# onee_rev1.net
KiCad netlist of a schematic drawn in EAGLE
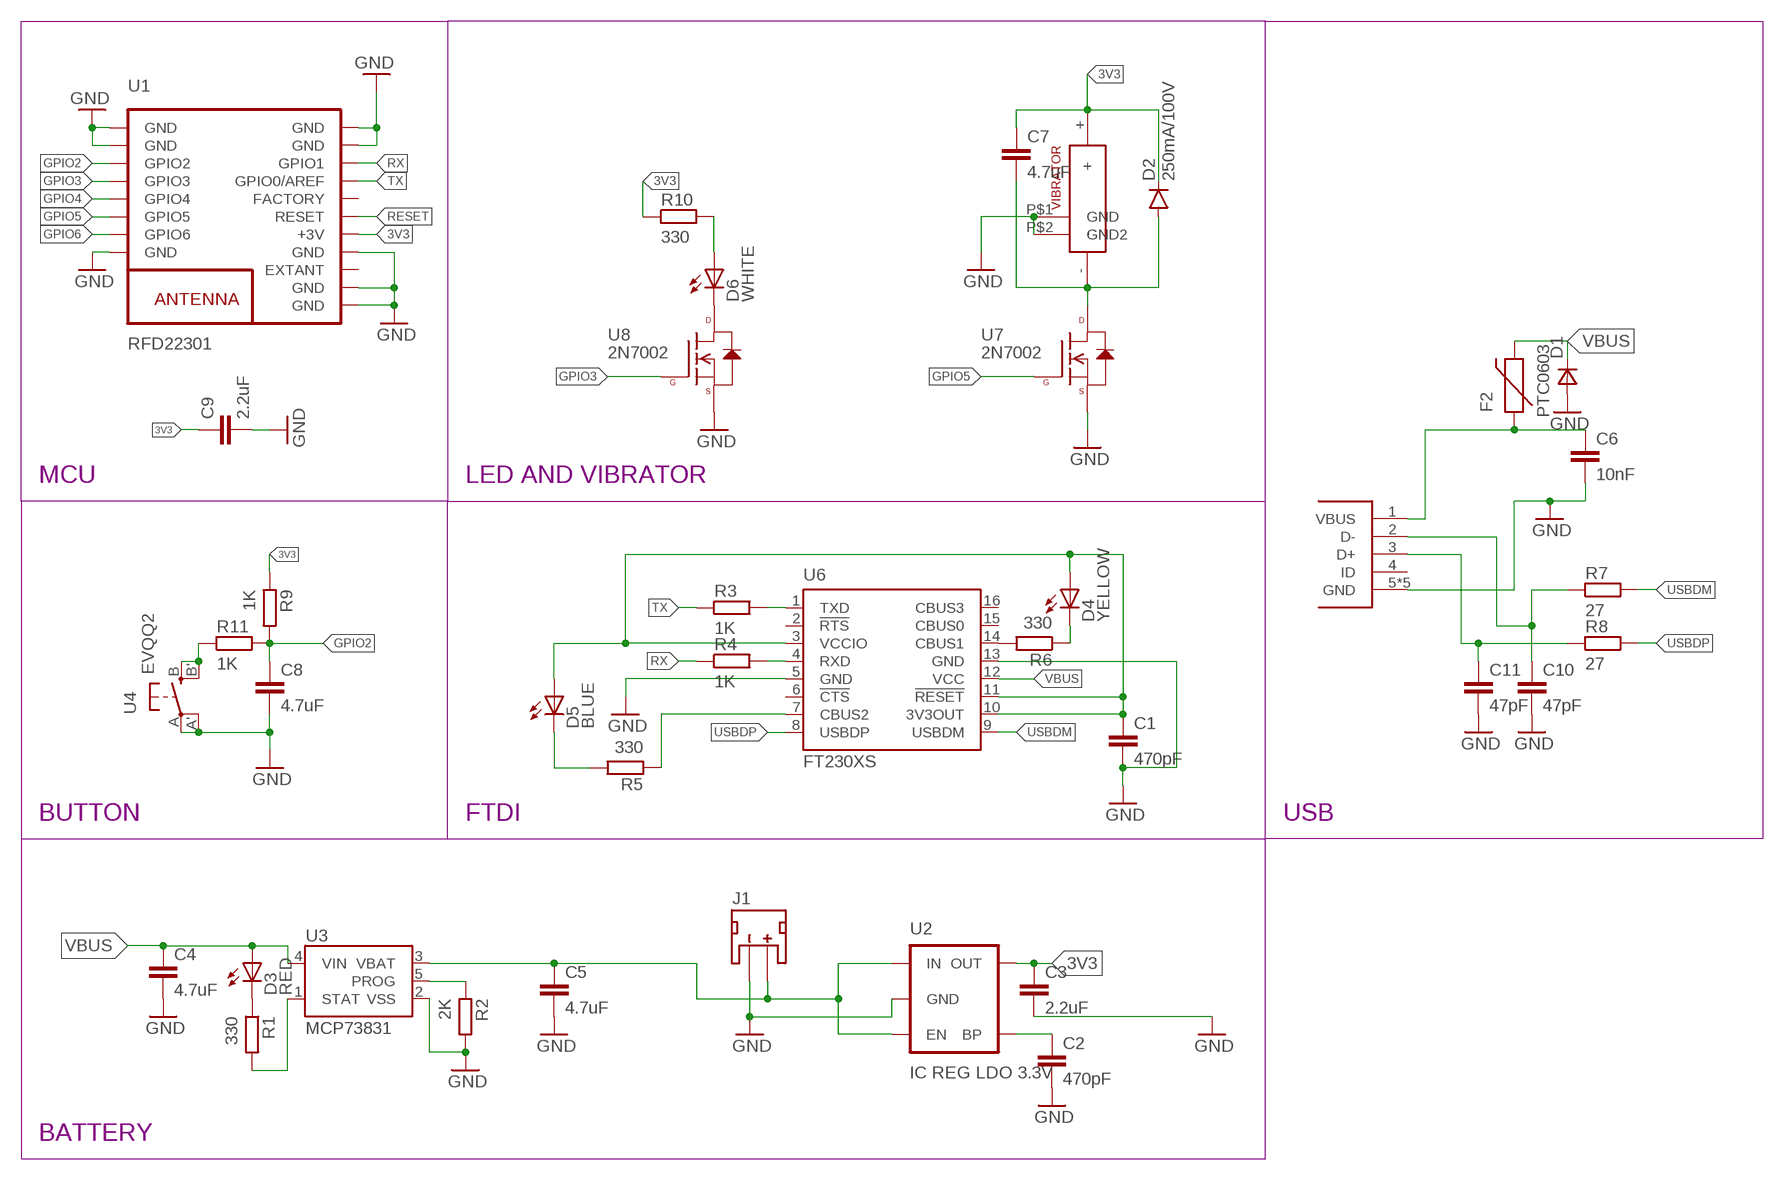
[diagram p0: schematic, sheet 1]

(export (version "E")
  (design (tool "Eeschema 10.0.6"))
  (components
    (comp (ref "C1")
      (value "470pF")
      (footprint "eagle-import:0603-CAP")
      (libsource (lib "eagle-import") (part "470PF-50V-5%(0603)SMD"))
    )
    (comp (ref "C2")
      (value "470pF")
      (footprint "eagle-import:0603-CAP")
      (libsource (lib "eagle-import") (part "470PF-50V-5%(0603)SMD"))
    )
    (comp (ref "C3")
      (value "2.2uF")
      (footprint "eagle-import:0603-CAP")
      (libsource (lib "eagle-import") (part "2.2UF-10V-20%(0603)"))
    )
    (comp (ref "C4")
      (value "4.7uF")
      (footprint "eagle-import:0603-CAP")
      (libsource (lib "eagle-import") (part "4.7UF-6.3V-10%(0603)0603"))
    )
    (comp (ref "C5")
      (value "4.7uF")
      (footprint "eagle-import:0603-CAP")
      (libsource (lib "eagle-import") (part "4.7UF-6.3V-10%(0603)0603"))
    )
    (comp (ref "C6")
      (value "10nF")
      (footprint "eagle-import:0603-CAP")
      (libsource (lib "eagle-import") (part "10NF/10000PF-50V-10%(0603)"))
    )
    (comp (ref "C7")
      (value "4.7uF")
      (footprint "eagle-import:0603-CAP")
      (libsource (lib "eagle-import") (part "4.7UF-6.3V-10%(0603)0603"))
    )
    (comp (ref "C8")
      (value "4.7uF")
      (footprint "eagle-import:0603-CAP")
      (libsource (lib "eagle-import") (part "4.7UF-6.3V-10%(0603)0603"))
    )
    (comp (ref "C9")
      (value "2.2uF")
      (footprint "eagle-import:0603-CAP")
      (libsource (lib "eagle-import") (part "2.2UF-10V-20%(0603)"))
    )
    (comp (ref "C10")
      (value "47pF")
      (footprint "eagle-import:0603-CAP")
      (libsource (lib "eagle-import") (part "47PF-50V-5%(0603)"))
    )
    (comp (ref "C11")
      (value "47pF")
      (footprint "eagle-import:0603-CAP")
      (libsource (lib "eagle-import") (part "47PF-50V-5%(0603)"))
    )
    (comp (ref "D1")
      (value "DSOD323")
      (footprint "eagle-import:SOD323")
      (fields (field (name "MPN") "CDSOD323-T05C"))
      (libsource (lib "eagle-import") (part "DSOD323"))
    )
    (comp (ref "D2")
      (value "250mA/100V")
      (footprint "eagle-import:SOD-323")
      (libsource (lib "eagle-import") (part "DIODEBAS16"))
    )
    (comp (ref "D3")
      (value "RED")
      (footprint "eagle-import:CHIP-LED0805")
      (libsource (lib "eagle-import") (part "LEDCHIP-LED0805"))
    )
    (comp (ref "D4")
      (value "YELLOW")
      (footprint "eagle-import:CHIP-LED0805")
      (libsource (lib "eagle-import") (part "LEDCHIP-LED0805"))
    )
    (comp (ref "D5")
      (value "BLUE")
      (footprint "eagle-import:CHIP-LED0805")
      (libsource (lib "eagle-import") (part "LEDCHIP-LED0805"))
    )
    (comp (ref "D6")
      (value "WHITE")
      (footprint "eagle-import:LED_SML0603")
      (libsource (lib "eagle-import") (part "LED_ESML0603"))
    )
    (comp (ref "F2")
      (value "PTC0603")
      (footprint "eagle-import:0603")
      (libsource (lib "eagle-import") (part "PTC0603"))
    )
    (comp (ref "J1")
      (value "BATTERY")
      (footprint "eagle-import:JST-2-SMD")
      (libsource (lib "eagle-import") (part "JST_2MM_MALE"))
    )
    (comp (ref "R1")
      (value "330")
      (footprint "eagle-import:R0603")
      (libsource (lib "eagle-import") (part "RESISTOR"))
    )
    (comp (ref "R2")
      (value "2K")
      (footprint "eagle-import:R0603")
      (libsource (lib "eagle-import") (part "RESISTOR"))
    )
    (comp (ref "R3")
      (value "1K")
      (footprint "eagle-import:R0603")
      (libsource (lib "eagle-import") (part "RESISTOR"))
    )
    (comp (ref "R4")
      (value "1K")
      (footprint "eagle-import:R0603")
      (libsource (lib "eagle-import") (part "RESISTOR"))
    )
    (comp (ref "R5")
      (value "330")
      (footprint "eagle-import:R0603")
      (libsource (lib "eagle-import") (part "RESISTOR"))
    )
    (comp (ref "R6")
      (value "330")
      (footprint "eagle-import:R0603")
      (libsource (lib "eagle-import") (part "RESISTOR"))
    )
    (comp (ref "R7")
      (value "27")
      (footprint "eagle-import:R0603")
      (libsource (lib "eagle-import") (part "RESISTOR"))
    )
    (comp (ref "R8")
      (value "27")
      (footprint "eagle-import:R0603")
      (libsource (lib "eagle-import") (part "RESISTOR"))
    )
    (comp (ref "R9")
      (value "1K")
      (footprint "eagle-import:R0603")
      (libsource (lib "eagle-import") (part "RESISTOR"))
    )
    (comp (ref "R10")
      (value "330")
      (footprint "eagle-import:R0603")
      (libsource (lib "eagle-import") (part "RESISTOR"))
    )
    (comp (ref "R11")
      (value "1K")
      (footprint "eagle-import:R0603")
      (libsource (lib "eagle-import") (part "RESISTOR"))
    )
    (comp (ref "U$2")
      (value "304-100")
      (footprint "eagle-import:304-100")
      (libsource (lib "eagle-import") (part "304-100"))
    )
    (comp (ref "U1")
      (value "RFD22301")
      (footprint "eagle-import:RFD22301")
      (libsource (lib "eagle-import") (part "RFD22301"))
    )
    (comp (ref "U2")
      (value "IC REG LDO 3.3V")
      (footprint "eagle-import:SOT23-5")
      (libsource (lib "eagle-import") (part "MIC52053.3V"))
    )
    (comp (ref "U3")
      (value "MCP73831")
      (footprint "eagle-import:SOT23-5")
      (libsource (lib "eagle-import") (part "MCP73831"))
    )
    (comp (ref "U4")
      (value "EVQQ2")
      (footprint "eagle-import:EVQ-Q2")
      (libsource (lib "eagle-import") (part "EVQQ2"))
    )
    (comp (ref "U5")
      (value "USB_MICROB")
      (footprint "eagle-import:USB_MICROB")
      (libsource (lib "eagle-import") (part "USB_MICROB"))
    )
    (comp (ref "U6")
      (value "FT230XS")
      (footprint "eagle-import:SSOP16")
      (libsource (lib "eagle-import") (part "FT230XS"))
    )
    (comp (ref "U7")
      (value "2N7002")
      (footprint "eagle-import:SOT23-3")
      (libsource (lib "eagle-import") (part "N-CHANNEL-MOSFET-BSS138"))
    )
    (comp (ref "U8")
      (value "2N7002")
      (footprint "eagle-import:SOT23-3")
      (libsource (lib "eagle-import") (part "N-CHANNEL-MOSFET-BSS138"))
    )
  )
  (nets
    (net (code "1") (name "3V3") (class "Default")
      (node (ref "C3") (pin "1") (pinfunction "1_1") (pintype "passive"))
      (node (ref "C7") (pin "1") (pinfunction "1_1") (pintype "passive"))
      (node (ref "C9") (pin "1") (pinfunction "1_1") (pintype "passive"))
      (node (ref "D2") (pin "C") (pinfunction "C_C") (pintype "passive"))
      (node (ref "R10") (pin "1") (pinfunction "1_1") (pintype "passive"))
      (node (ref "R9") (pin "1") (pinfunction "1_1") (pintype "passive"))
      (node (ref "U$2") (pin "+") (pinfunction "+_+") (pintype "bidirectional"))
      (node (ref "U1") (pin "13") (pinfunction "+3V_13") (pintype "power_in"))
      (node (ref "U2") (pin "5") (pinfunction "OUT_5") (pintype "passive"))
    )
    (net (code "2") (name "GND") (class "Default")
      (node (ref "C1") (pin "2") (pinfunction "2_2") (pintype "passive"))
      (node (ref "C10") (pin "2") (pinfunction "2_2") (pintype "passive"))
      (node (ref "C11") (pin "2") (pinfunction "2_2") (pintype "passive"))
      (node (ref "C2") (pin "2") (pinfunction "2_2") (pintype "passive"))
      (node (ref "C3") (pin "2") (pinfunction "2_2") (pintype "passive"))
      (node (ref "C4") (pin "2") (pinfunction "2_2") (pintype "passive"))
      (node (ref "C5") (pin "2") (pinfunction "2_2") (pintype "passive"))
      (node (ref "C6") (pin "2") (pinfunction "2_2") (pintype "passive"))
      (node (ref "C8") (pin "2") (pinfunction "2_2") (pintype "passive"))
      (node (ref "C9") (pin "2") (pinfunction "2_2") (pintype "passive"))
      (node (ref "D1") (pin "2") (pinfunction "A_2") (pintype "passive"))
      (node (ref "J1") (pin "1") (pinfunction "-_1") (pintype "bidirectional"))
      (node (ref "R2") (pin "2") (pinfunction "2_2") (pintype "passive"))
      (node (ref "U$2") (pin "P$1") (pinfunction "GND_P$1") (pintype "bidirectional"))
      (node (ref "U$2") (pin "P$2") (pinfunction "GND2_P$2") (pintype "bidirectional"))
      (node (ref "U1") (pin "1") (pinfunction "GND_1") (pintype "power_in"))
      (node (ref "U1") (pin "10") (pinfunction "GND_10") (pintype "power_in"))
      (node (ref "U1") (pin "12") (pinfunction "GND_12") (pintype "power_in"))
      (node (ref "U1") (pin "18") (pinfunction "GND_18") (pintype "power_in"))
      (node (ref "U1") (pin "19") (pinfunction "GND_19") (pintype "power_in"))
      (node (ref "U1") (pin "2") (pinfunction "GND_2") (pintype "power_in"))
      (node (ref "U1") (pin "8") (pinfunction "GND_8") (pintype "power_in"))
      (node (ref "U1") (pin "9") (pinfunction "GND_9") (pintype "power_in"))
      (node (ref "U2") (pin "2") (pinfunction "GND_2") (pintype "input"))
      (node (ref "U3") (pin "2") (pinfunction "VSS_2") (pintype "power_in"))
      (node (ref "U4") (pin "A") (pinfunction "P_A") (pintype "passive"))
      (node (ref "U4") (pin "A'") (pinfunction "P1_A'") (pintype "passive"))
      (node (ref "U5") (pin "5") (pinfunction "GND_5") (pintype "bidirectional"))
      (node (ref "U5") (pin "P$6") (pinfunction "GND_P$6") (pintype "bidirectional"))
      (node (ref "U5") (pin "P$7") (pinfunction "GND_P$7") (pintype "bidirectional"))
      (node (ref "U5") (pin "P$8") (pinfunction "GND_P$8") (pintype "bidirectional"))
      (node (ref "U5") (pin "P$9") (pinfunction "GND_P$9") (pintype "bidirectional"))
      (node (ref "U6") (pin "13") (pinfunction "GND_13") (pintype "power_in"))
      (node (ref "U6") (pin "5") (pinfunction "GND_5") (pintype "power_in"))
      (node (ref "U7") (pin "2") (pinfunction "S_2") (pintype "passive"))
      (node (ref "U8") (pin "2") (pinfunction "S_2") (pintype "passive"))
    )
    (net (code "3") (name "GPIO2") (class "Default")
      (node (ref "C8") (pin "1") (pinfunction "1_1") (pintype "passive"))
      (node (ref "R11") (pin "2") (pinfunction "2_2") (pintype "passive"))
      (node (ref "R9") (pin "2") (pinfunction "2_2") (pintype "passive"))
      (node (ref "U1") (pin "3") (pinfunction "GPIO2_3") (pintype "bidirectional"))
    )
    (net (code "4") (name "GPIO3") (class "Default")
      (node (ref "U1") (pin "4") (pinfunction "GPIO3_4") (pintype "bidirectional"))
      (node (ref "U8") (pin "1") (pinfunction "G_1") (pintype "passive"))
    )
    (net (code "5") (name "GPIO4") (class "Default")
      (node (ref "U1") (pin "5") (pinfunction "GPIO4_5") (pintype "bidirectional"))
    )
    (net (code "6") (name "GPIO5") (class "Default")
      (node (ref "U1") (pin "6") (pinfunction "GPIO5_6") (pintype "bidirectional"))
      (node (ref "U7") (pin "1") (pinfunction "G_1") (pintype "passive"))
    )
    (net (code "7") (name "GPIO6") (class "Default")
      (node (ref "U1") (pin "7") (pinfunction "GPIO6_7") (pintype "bidirectional"))
    )
    (net (code "8") (name "Net-(D3-PadC)") (class "Default")
      (node (ref "D3") (pin "C") (pinfunction "C_C") (pintype "passive"))
      (node (ref "R1") (pin "1") (pinfunction "1_1") (pintype "passive"))
    )
    (net (code "9") (name "Net-(D4-PadC)") (class "Default")
      (node (ref "D4") (pin "C") (pinfunction "C_C") (pintype "passive"))
      (node (ref "R6") (pin "1") (pinfunction "1_1") (pintype "passive"))
    )
    (net (code "10") (name "Net-(D5-PadC)") (class "Default")
      (node (ref "D5") (pin "C") (pinfunction "C_C") (pintype "passive"))
      (node (ref "R5") (pin "2") (pinfunction "2_2") (pintype "passive"))
    )
    (net (code "11") (name "Net-(D6-PadA)") (class "Default")
      (node (ref "D6") (pin "A") (pinfunction "A_A") (pintype "passive"))
      (node (ref "R10") (pin "2") (pinfunction "2_2") (pintype "passive"))
    )
    (net (code "12") (name "Net-(J1-+)") (class "Default")
      (node (ref "C5") (pin "1") (pinfunction "1_1") (pintype "passive"))
      (node (ref "J1") (pin "2") (pinfunction "+_2") (pintype "bidirectional"))
      (node (ref "U2") (pin "1") (pinfunction "IN_1") (pintype "input"))
      (node (ref "U2") (pin "3") (pinfunction "EN_3") (pintype "input"))
      (node (ref "U3") (pin "3") (pinfunction "VBAT_3") (pintype "power_in"))
    )
    (net (code "13") (name "Net-(U2-BP)") (class "Default")
      (node (ref "C2") (pin "1") (pinfunction "1_1") (pintype "passive"))
      (node (ref "U2") (pin "4") (pinfunction "BP_4") (pintype "input"))
    )
    (net (code "14") (name "Net-(U3-PROG)") (class "Default")
      (node (ref "R2") (pin "1") (pinfunction "1_1") (pintype "passive"))
      (node (ref "U3") (pin "5") (pinfunction "PROG_5") (pintype "input"))
    )
    (net (code "15") (name "Net-(U3-STAT)") (class "Default")
      (node (ref "R1") (pin "2") (pinfunction "2_2") (pintype "passive"))
      (node (ref "U3") (pin "1") (pinfunction "STAT_1") (pintype "output"))
    )
    (net (code "16") (name "Net-(U4-S)") (class "Default")
      (node (ref "R11") (pin "1") (pinfunction "1_1") (pintype "passive"))
      (node (ref "U4") (pin "B") (pinfunction "S_B") (pintype "passive"))
      (node (ref "U4") (pin "B'") (pinfunction "S1_B'") (pintype "passive"))
    )
    (net (code "17") (name "Net-(U5-D+)") (class "Default")
      (node (ref "C11") (pin "1") (pinfunction "1_1") (pintype "passive"))
      (node (ref "R8") (pin "1") (pinfunction "1_1") (pintype "passive"))
      (node (ref "U5") (pin "3") (pinfunction "D+_3") (pintype "bidirectional"))
    )
    (net (code "18") (name "Net-(U5-D-)") (class "Default")
      (node (ref "C10") (pin "1") (pinfunction "1_1") (pintype "passive"))
      (node (ref "R7") (pin "1") (pinfunction "1_1") (pintype "passive"))
      (node (ref "U5") (pin "2") (pinfunction "D-_2") (pintype "bidirectional"))
    )
    (net (code "19") (name "Net-(U5-VBUS)") (class "Default")
      (node (ref "C6") (pin "1") (pinfunction "1_1") (pintype "passive"))
      (node (ref "F2") (pin "1") (pinfunction "1_1") (pintype "bidirectional"))
      (node (ref "U5") (pin "1") (pinfunction "VBUS_1") (pintype "bidirectional"))
    )
    (net (code "20") (name "Net-(U6-3V3OUT)") (class "Default")
      (node (ref "C1") (pin "1") (pinfunction "1_1") (pintype "passive"))
      (node (ref "D4") (pin "A") (pinfunction "A_A") (pintype "passive"))
      (node (ref "D5") (pin "A") (pinfunction "A_A") (pintype "passive"))
      (node (ref "U6") (pin "10") (pinfunction "3V3OUT_10") (pintype "output"))
      (node (ref "U6") (pin "11") (pinfunction "~{RESET}_11") (pintype "input"))
      (node (ref "U6") (pin "3") (pinfunction "VCCIO_3") (pintype "power_in"))
    )
    (net (code "21") (name "Net-(U6-CBUS1)") (class "Default")
      (node (ref "R6") (pin "2") (pinfunction "2_2") (pintype "passive"))
      (node (ref "U6") (pin "14") (pinfunction "CBUS1_14") (pintype "bidirectional"))
    )
    (net (code "22") (name "Net-(U6-CBUS2)") (class "Default")
      (node (ref "R5") (pin "1") (pinfunction "1_1") (pintype "passive"))
      (node (ref "U6") (pin "7") (pinfunction "CBUS2_7") (pintype "bidirectional"))
    )
    (net (code "23") (name "Net-(U6-RXD)") (class "Default")
      (node (ref "R4") (pin "2") (pinfunction "2_2") (pintype "passive"))
      (node (ref "U6") (pin "4") (pinfunction "RXD_4") (pintype "input"))
    )
    (net (code "24") (name "Net-(U6-TXD)") (class "Default")
      (node (ref "R3") (pin "2") (pinfunction "2_2") (pintype "passive"))
      (node (ref "U6") (pin "1") (pinfunction "TXD_1") (pintype "output"))
    )
    (net (code "25") (name "Net-(U7-D)") (class "Default")
      (node (ref "C7") (pin "2") (pinfunction "2_2") (pintype "passive"))
      (node (ref "D2") (pin "A") (pinfunction "A_A") (pintype "passive"))
      (node (ref "U$2") (pin "-") (pinfunction "-_-") (pintype "bidirectional"))
      (node (ref "U7") (pin "3") (pinfunction "D_3") (pintype "passive"))
    )
    (net (code "26") (name "Net-(U8-D)") (class "Default")
      (node (ref "D6") (pin "C") (pinfunction "C_C") (pintype "passive"))
      (node (ref "U8") (pin "3") (pinfunction "D_3") (pintype "passive"))
    )
    (net (code "27") (name "RESET") (class "Default")
      (node (ref "U1") (pin "14") (pinfunction "RESET_14") (pintype "bidirectional"))
    )
    (net (code "28") (name "RX") (class "Default")
      (node (ref "R4") (pin "1") (pinfunction "1_1") (pintype "passive"))
      (node (ref "U1") (pin "17") (pinfunction "GPIO1_17") (pintype "bidirectional"))
    )
    (net (code "29") (name "TX") (class "Default")
      (node (ref "R3") (pin "1") (pinfunction "1_1") (pintype "passive"))
      (node (ref "U1") (pin "16") (pinfunction "GPIO0/AREF_16") (pintype "bidirectional"))
    )
    (net (code "30") (name "USBDM") (class "Default")
      (node (ref "R7") (pin "2") (pinfunction "2_2") (pintype "passive"))
      (node (ref "U6") (pin "9") (pinfunction "USBDM_9") (pintype "input"))
    )
    (net (code "31") (name "USBDP") (class "Default")
      (node (ref "R8") (pin "2") (pinfunction "2_2") (pintype "passive"))
      (node (ref "U6") (pin "8") (pinfunction "USBDP_8") (pintype "input"))
    )
    (net (code "32") (name "VBUS") (class "Default")
      (node (ref "C4") (pin "1") (pinfunction "1_1") (pintype "passive"))
      (node (ref "D1") (pin "1") (pinfunction "C_1") (pintype "passive"))
      (node (ref "D3") (pin "A") (pinfunction "A_A") (pintype "passive"))
      (node (ref "F2") (pin "2") (pinfunction "2_2") (pintype "bidirectional"))
      (node (ref "U3") (pin "4") (pinfunction "VIN_4") (pintype "power_in"))
      (node (ref "U6") (pin "12") (pinfunction "VCC_12") (pintype "power_in"))
    )
    (net (code "33") (name "unconnected-(J1-PAD1-PadNC1)") (class "Default")
      (node (ref "J1") (pin "NC1") (pinfunction "PAD1_NC1") (pintype "bidirectional"))
    )
    (net (code "34") (name "unconnected-(J1-PAD2-PadNC2)") (class "Default")
      (node (ref "J1") (pin "NC2") (pinfunction "PAD2_NC2") (pintype "bidirectional"))
    )
    (net (code "35") (name "unconnected-(U1-EXTANT-Pad11)") (class "Default")
      (node (ref "U1") (pin "11") (pinfunction "EXTANT_11") (pintype "no_connect"))
    )
    (net (code "36") (name "unconnected-(U1-FACTORY-Pad15)") (class "Default")
      (node (ref "U1") (pin "15") (pinfunction "FACTORY_15") (pintype "bidirectional"))
    )
    (net (code "37") (name "unconnected-(U5-ID-Pad4)") (class "Default")
      (node (ref "U5") (pin "4") (pinfunction "ID_4") (pintype "bidirectional"))
    )
    (net (code "38") (name "unconnected-(U6-CBUS0-Pad15)") (class "Default")
      (node (ref "U6") (pin "15") (pinfunction "CBUS0_15") (pintype "bidirectional"))
    )
    (net (code "39") (name "unconnected-(U6-CBUS3-Pad16)") (class "Default")
      (node (ref "U6") (pin "16") (pinfunction "CBUS3_16") (pintype "bidirectional"))
    )
    (net (code "40") (name "unconnected-(U6-~{CTS}-Pad6)") (class "Default")
      (node (ref "U6") (pin "6") (pinfunction "~{CTS}_6") (pintype "input"))
    )
    (net (code "41") (name "unconnected-(U6-~{RTS}-Pad2)") (class "Default")
      (node (ref "U6") (pin "2") (pinfunction "~{RTS}_2") (pintype "output"))
    )
  )
)
